# SCH_Nfc-card_2024-09-17.net
KiCad netlist of a schematic drawn in EasyEDA
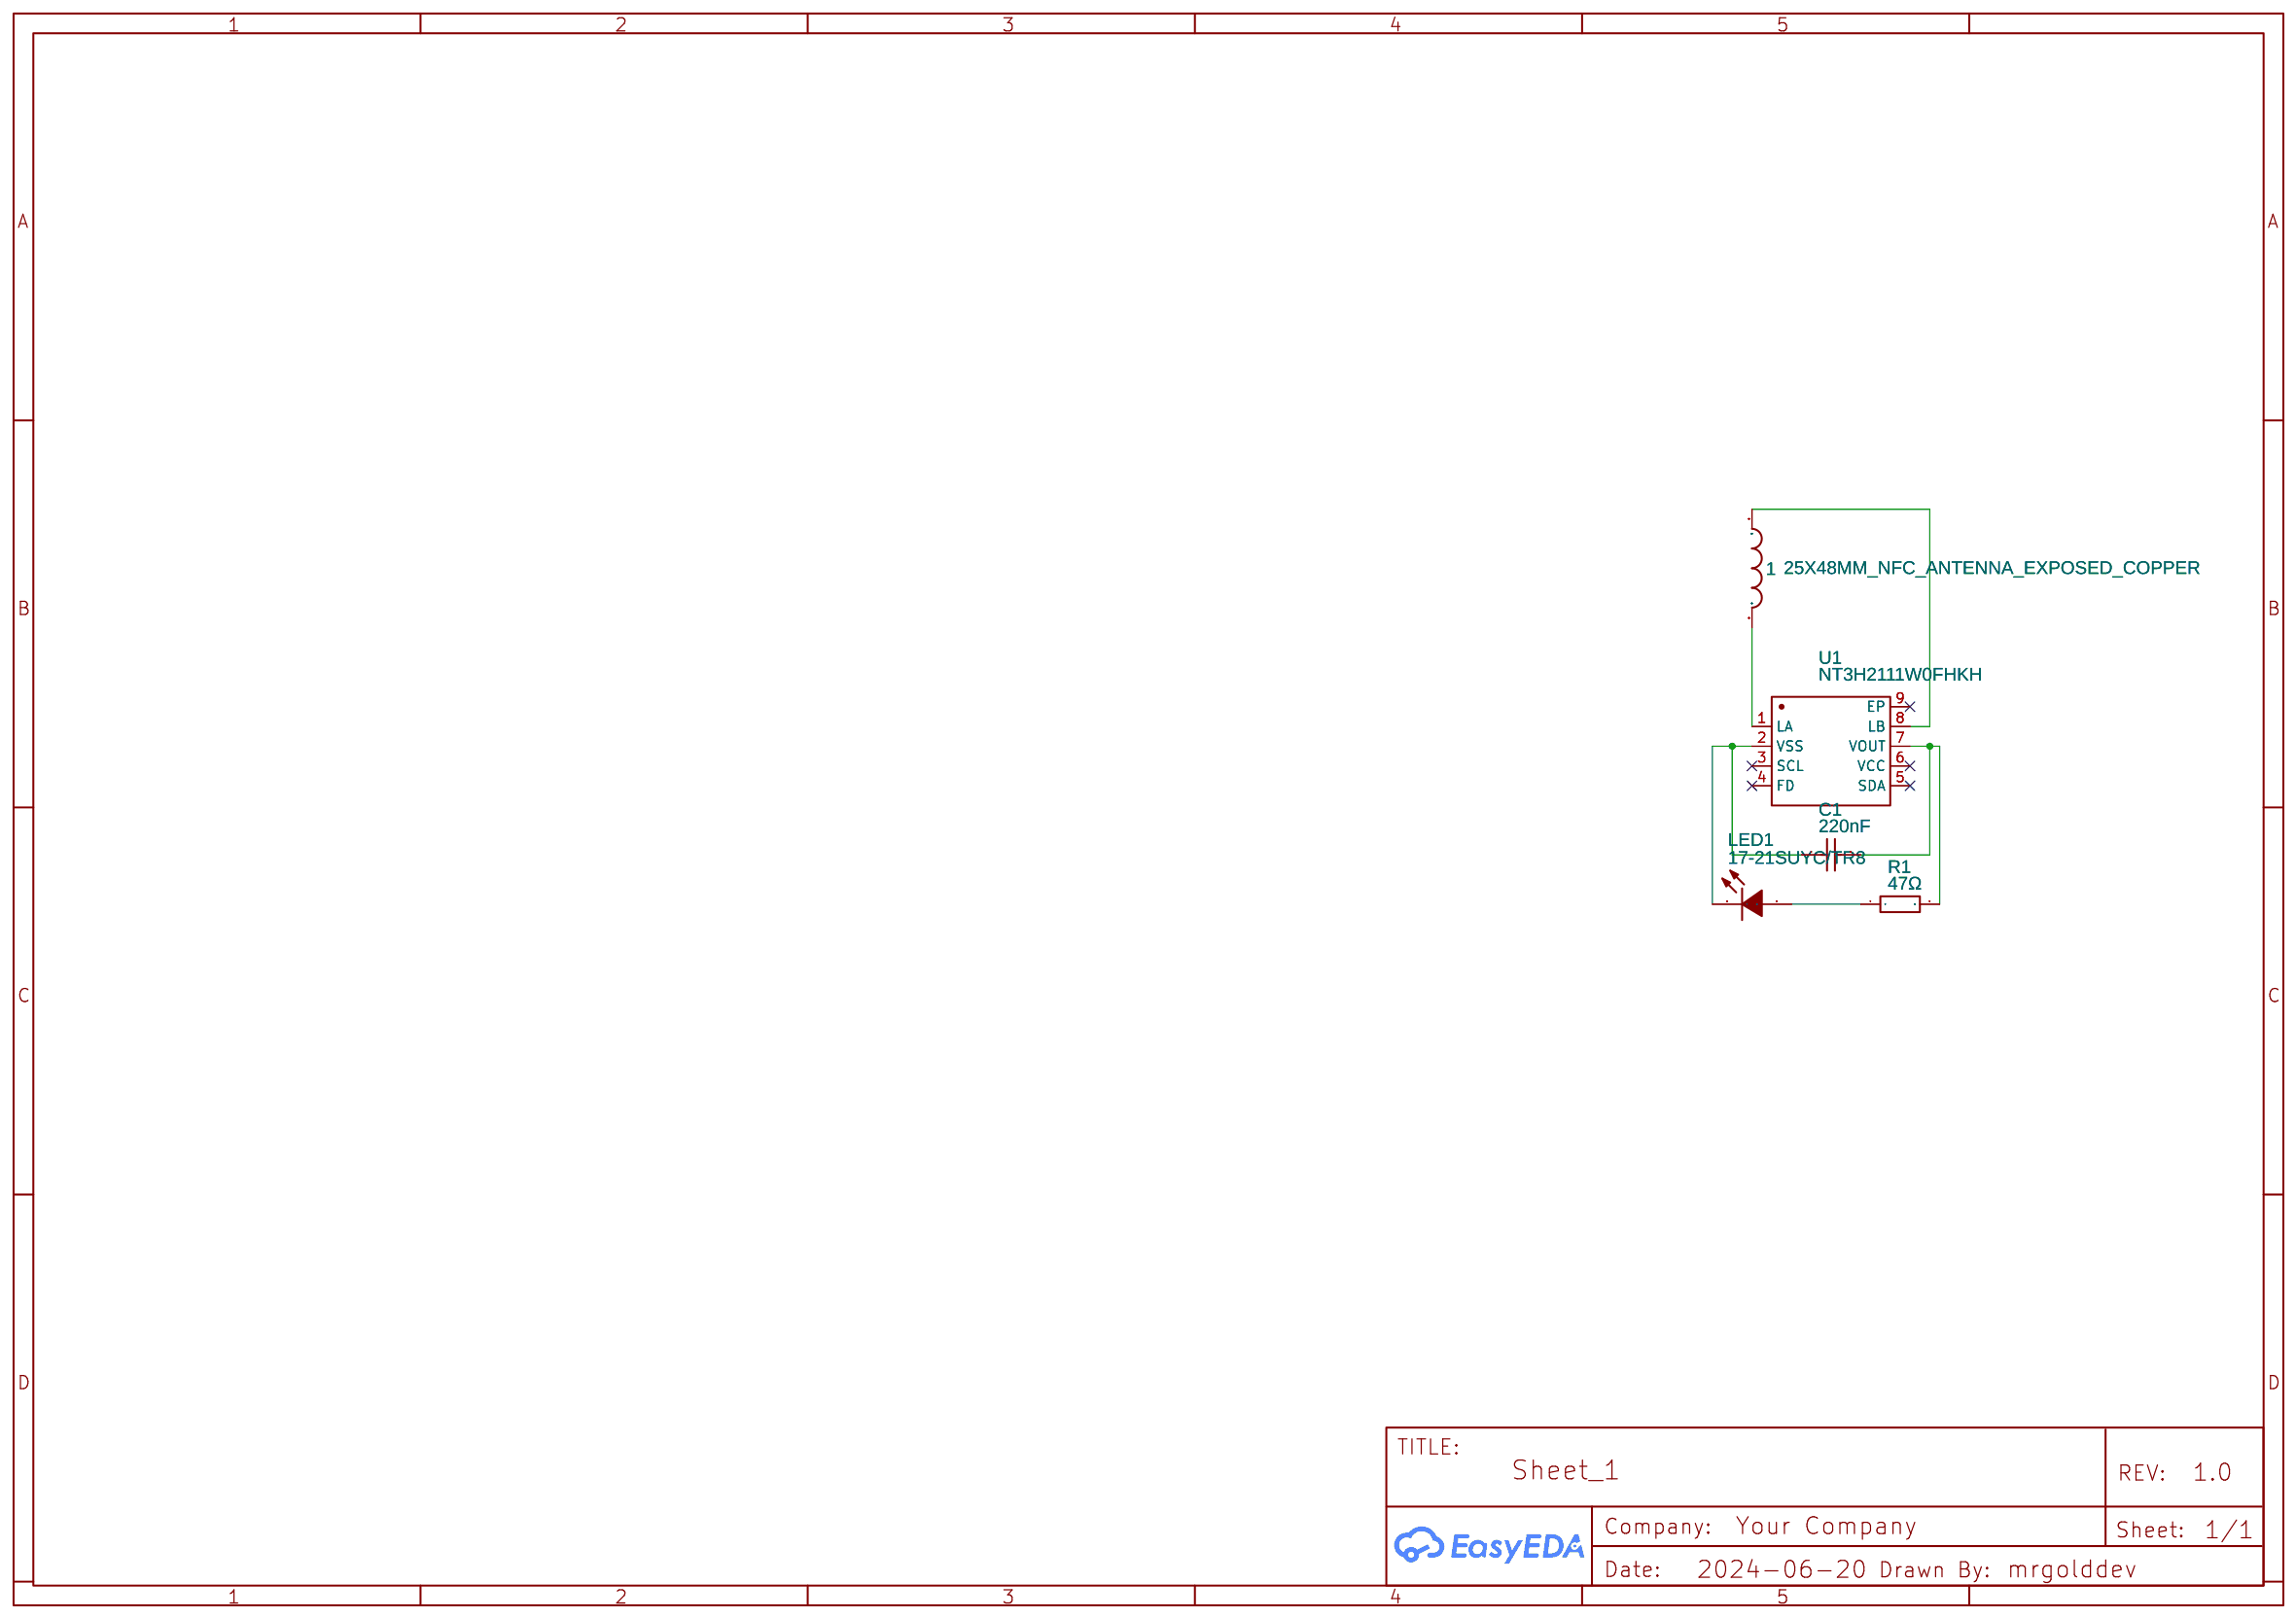
[diagram p0: schematic sheet]

(export (version "E")
  (design (tool "Eeschema 10.0.6"))
  (components
    (comp (ref "1")
      (value "25X48MM_NFC_ANTENNA_EXPOSED_COPPER")
      (libsource (lib "") (part "25X48MM_NFC_ANTENNA_EXPOSED_COPPER"))
    )
    (comp (ref "C1")
      (value "220nF")
      (fields
        (field (name "Manufacturer Part") "CL10B224KA8NNNC")
        (field (name "Manufacturer") "SAMSUNG(三星)")
      )
      (libsource (lib "") (part "CL10B224KA8NNNC"))
    )
    (comp (ref "LED1")
      (value "17-21SUYC/TR8")
      (fields (field (name "Manufacturer Part") "KT-0805黄灯") (field (name "Manufacturer") "KENTO"))
      (libsource (lib "") (part "17-21SUYC/TR8"))
    )
    (comp (ref "R1")
      (value "47Ω")
      (fields
        (field (name "Manufacturer Part") "0603WAF470JT5E")
        (field (name "Manufacturer") "UNI-ROYAL(厚声)")
      )
      (libsource (lib "") (part "0603WAF470JT5E"))
    )
    (comp (ref "U1")
      (value "NT3H2111W0FHKH")
      (fields (field (name "Manufacturer") "NXP(恩智浦)"))
      (libsource (lib "") (part "NT3H2111W0FHKH"))
    )
  )
  (nets
    (net (code "1") (name "Net-(LED1-+)") (class "Default")
      (node (ref "LED1") (pin "1") (pinfunction "+_1") (pintype "unspecified"))
      (node (ref "R1") (pin "1") (pinfunction "1_1") (pintype "input"))
    )
    (net (code "2") (name "Net-(LED1--)") (class "Default")
      (node (ref "C1") (pin "1") (pinfunction "1_1") (pintype "input"))
      (node (ref "LED1") (pin "2") (pinfunction "-_2") (pintype "unspecified"))
      (node (ref "U1") (pin "2") (pinfunction "VSS_2") (pintype "unspecified"))
    )
    (net (code "3") (name "Net-(U1-LA)") (class "Default")
      (node (ref "1") (pin "P$2") (pinfunction "P$2_P$2") (pintype "bidirectional"))
      (node (ref "U1") (pin "1") (pinfunction "LA_1") (pintype "unspecified"))
    )
    (net (code "4") (name "Net-(U1-LB)") (class "Default")
      (node (ref "1") (pin "P$1") (pinfunction "P$1_P$1") (pintype "bidirectional"))
      (node (ref "U1") (pin "8") (pinfunction "LB_8") (pintype "unspecified"))
    )
    (net (code "5") (name "Net-(U1-VOUT)") (class "Default")
      (node (ref "C1") (pin "2") (pinfunction "2_2") (pintype "input"))
      (node (ref "R1") (pin "2") (pinfunction "2_2") (pintype "input"))
      (node (ref "U1") (pin "7") (pinfunction "VOUT_7") (pintype "unspecified"))
    )
    (net (code "6") (name "unconnected-(U1-EP-Pad9)") (class "Default")
      (node (ref "U1") (pin "9") (pinfunction "EP_9") (pintype "unspecified+no_connect"))
    )
    (net (code "7") (name "unconnected-(U1-FD-Pad4)") (class "Default")
      (node (ref "U1") (pin "4") (pinfunction "FD_4") (pintype "unspecified+no_connect"))
    )
    (net (code "8") (name "unconnected-(U1-SCL-Pad3)") (class "Default")
      (node (ref "U1") (pin "3") (pinfunction "SCL_3") (pintype "unspecified+no_connect"))
    )
    (net (code "9") (name "unconnected-(U1-SDA-Pad5)") (class "Default")
      (node (ref "U1") (pin "5") (pinfunction "SDA_5") (pintype "unspecified+no_connect"))
    )
    (net (code "10") (name "unconnected-(U1-VCC-Pad6)") (class "Default")
      (node (ref "U1") (pin "6") (pinfunction "VCC_6") (pintype "unspecified+no_connect"))
    )
  )
)
